# sapflux_base_v2.net
KiCad netlist of a schematic drawn in EAGLE
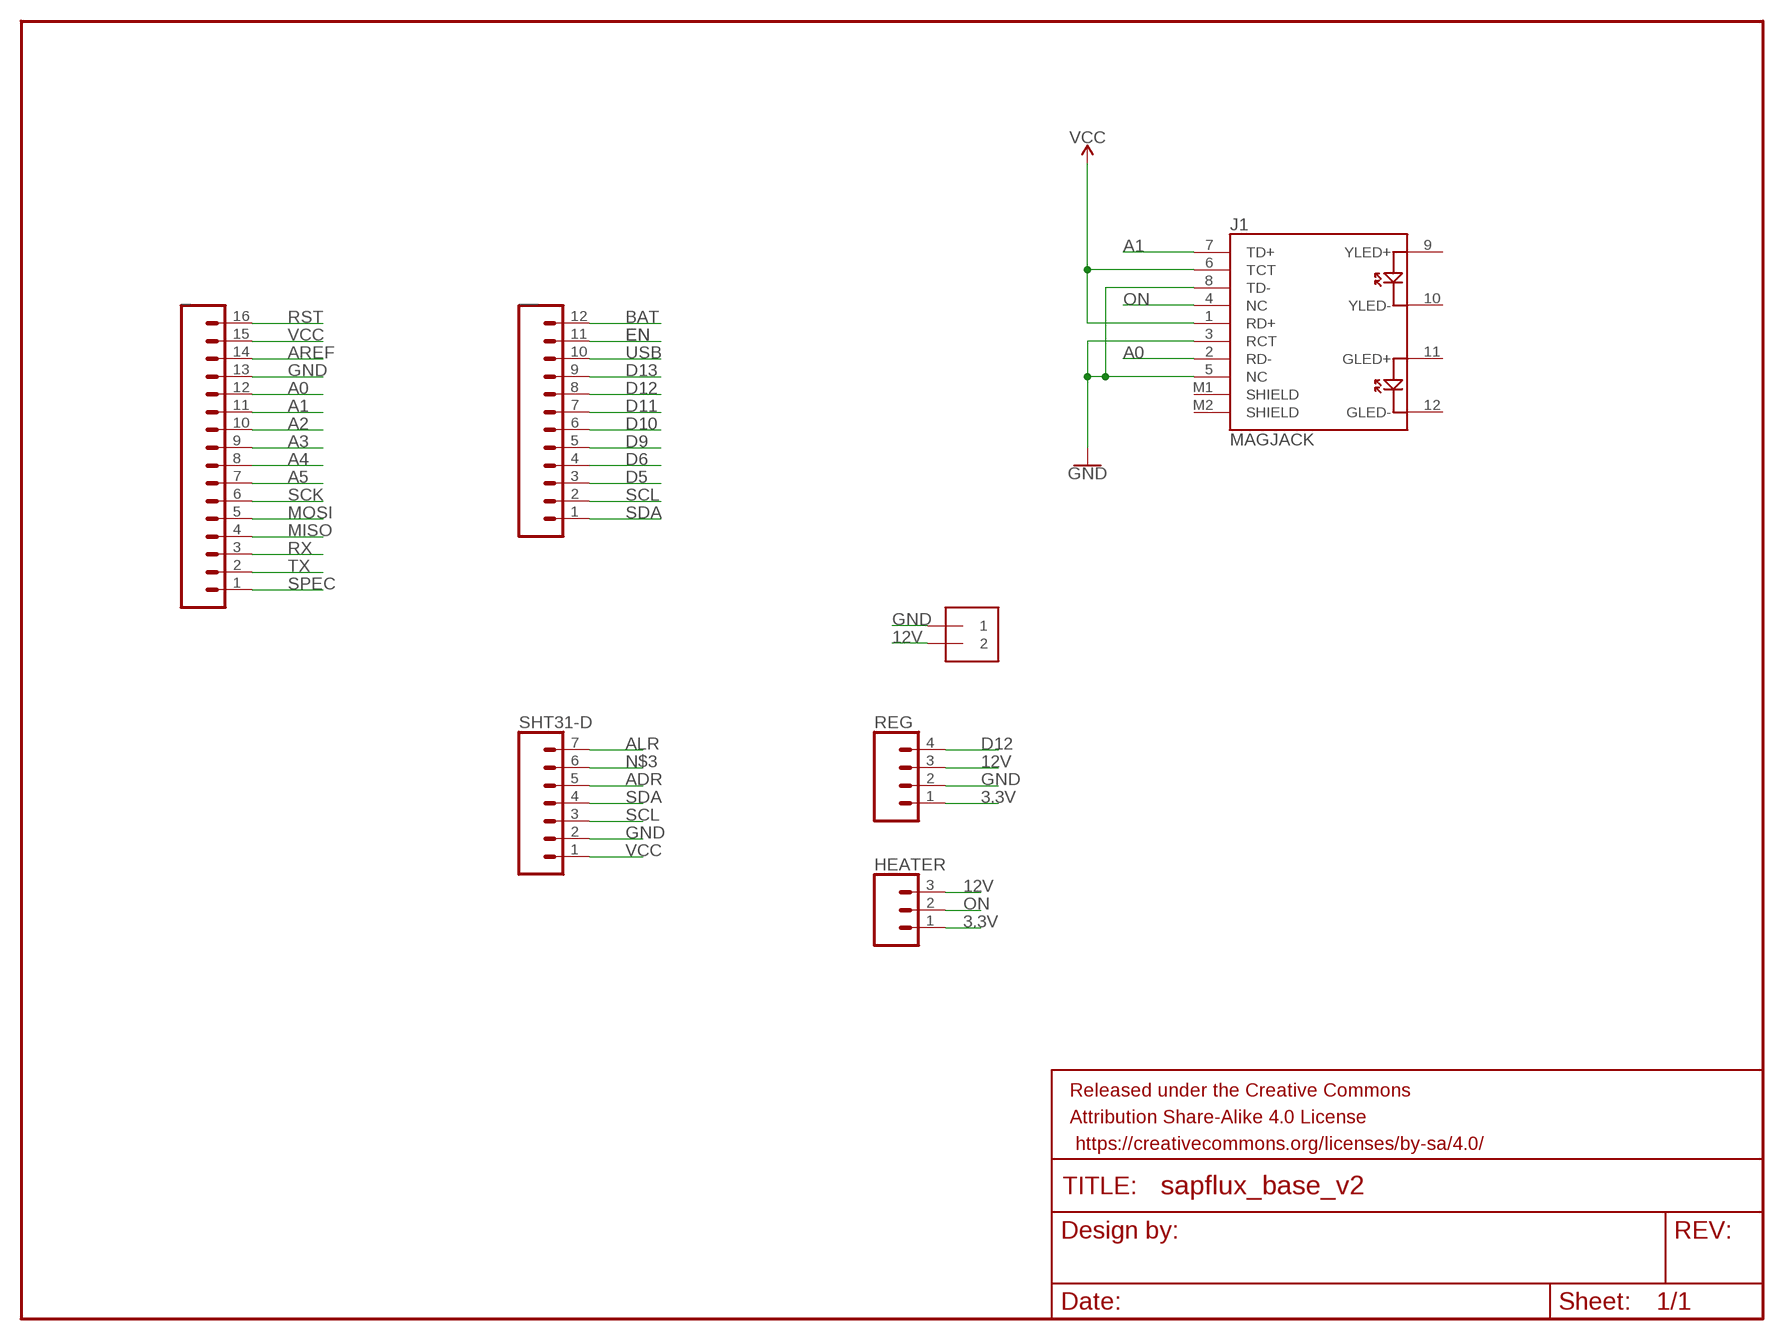
[diagram p0: schematic, sheet 1]

(export (version "E")
  (design (tool "Eeschema 10.0.6"))
  (components
    (comp (ref ".")
      (value "1X2-3.5MM")
      (footprint "eagle-import:1X2-3.5MM")
      (libsource (lib "eagle-import") (part "1X2-3.5MM"))
    )
    (comp (ref "FRAME1")
      (value "FRAME-LETTER")
      (footprint "eagle-import:CREATIVE_COMMONS")
      (libsource (lib "eagle-import") (part "FRAME-LETTER"))
    )
    (comp (ref "HEATER")
      (value "CONN_03")
      (footprint "eagle-import:1X03")
      (libsource (lib "eagle-import") (part "CONN_03"))
    )
    (comp (ref "J1")
      (value "MAGJACK")
      (footprint "eagle-import:MAGJACK")
      (libsource (lib "eagle-import") (part "MAGJACK"))
    )
    (comp (ref "REG")
      (value "CONN_04")
      (footprint "eagle-import:1X04")
      (libsource (lib "eagle-import") (part "CONN_04"))
    )
    (comp (ref "SHT31-D")
      (value "CONN_07")
      (footprint "eagle-import:1X07")
      (libsource (lib "eagle-import") (part "CONN_07"))
    )
    (comp (ref "_")
      (value "CONN_16")
      (footprint "eagle-import:1X16")
      (libsource (lib "eagle-import") (part "CONN_16"))
    )
    (comp (ref "__")
      (value "CONN_12")
      (footprint "eagle-import:1X12")
      (libsource (lib "eagle-import") (part "CONN_12"))
    )
  )
  (nets
    (net (code "1") (name "/3.3V") (class "Default")
      (node (ref "HEATER") (pin "1") (pinfunction "1_1") (pintype "passive"))
      (node (ref "REG") (pin "1") (pinfunction "1_1") (pintype "passive"))
    )
    (net (code "2") (name "/12V") (class "Default")
      (node (ref ".") (pin "2") (pinfunction "2_2") (pintype "passive"))
      (node (ref "HEATER") (pin "3") (pinfunction "3_3") (pintype "passive"))
      (node (ref "REG") (pin "3") (pinfunction "3_3") (pintype "passive"))
    )
    (net (code "3") (name "/A0") (class "Default")
      (node (ref "J1") (pin "2") (pinfunction "RD-_2") (pintype "bidirectional"))
      (node (ref "_") (pin "12") (pinfunction "12_12") (pintype "passive"))
    )
    (net (code "4") (name "/A1") (class "Default")
      (node (ref "J1") (pin "7") (pinfunction "TD+_7") (pintype "bidirectional"))
      (node (ref "_") (pin "11") (pinfunction "11_11") (pintype "passive"))
    )
    (net (code "5") (name "/A2") (class "Default")
      (node (ref "_") (pin "10") (pinfunction "10_10") (pintype "passive"))
    )
    (net (code "6") (name "/A3") (class "Default")
      (node (ref "_") (pin "9") (pinfunction "9_9") (pintype "passive"))
    )
    (net (code "7") (name "/A4") (class "Default")
      (node (ref "_") (pin "8") (pinfunction "8_8") (pintype "passive"))
    )
    (net (code "8") (name "/A5") (class "Default")
      (node (ref "_") (pin "7") (pinfunction "7_7") (pintype "passive"))
    )
    (net (code "9") (name "/ADR") (class "Default")
      (node (ref "SHT31-D") (pin "5") (pinfunction "5_5") (pintype "passive"))
    )
    (net (code "10") (name "/ALR") (class "Default")
      (node (ref "SHT31-D") (pin "7") (pinfunction "7_7") (pintype "passive"))
    )
    (net (code "11") (name "/AREF") (class "Default")
      (node (ref "_") (pin "14") (pinfunction "14_14") (pintype "passive"))
    )
    (net (code "12") (name "/BAT") (class "Default")
      (node (ref "__") (pin "12") (pinfunction "12_12") (pintype "passive"))
    )
    (net (code "13") (name "/D5") (class "Default")
      (node (ref "__") (pin "3") (pinfunction "3_3") (pintype "passive"))
    )
    (net (code "14") (name "/D6") (class "Default")
      (node (ref "__") (pin "4") (pinfunction "4_4") (pintype "passive"))
    )
    (net (code "15") (name "/D9") (class "Default")
      (node (ref "__") (pin "5") (pinfunction "5_5") (pintype "passive"))
    )
    (net (code "16") (name "/D10") (class "Default")
      (node (ref "__") (pin "6") (pinfunction "6_6") (pintype "passive"))
    )
    (net (code "17") (name "/D11") (class "Default")
      (node (ref "__") (pin "7") (pinfunction "7_7") (pintype "passive"))
    )
    (net (code "18") (name "/D12") (class "Default")
      (node (ref "REG") (pin "4") (pinfunction "4_4") (pintype "passive"))
      (node (ref "__") (pin "8") (pinfunction "8_8") (pintype "passive"))
    )
    (net (code "19") (name "/D13") (class "Default")
      (node (ref "__") (pin "9") (pinfunction "9_9") (pintype "passive"))
    )
    (net (code "20") (name "/EN") (class "Default")
      (node (ref "__") (pin "11") (pinfunction "11_11") (pintype "passive"))
    )
    (net (code "21") (name "/MISO") (class "Default")
      (node (ref "_") (pin "4") (pinfunction "4_4") (pintype "passive"))
    )
    (net (code "22") (name "/MOSI") (class "Default")
      (node (ref "_") (pin "5") (pinfunction "5_5") (pintype "passive"))
    )
    (net (code "23") (name "/N$3") (class "Default")
      (node (ref "SHT31-D") (pin "6") (pinfunction "6_6") (pintype "passive"))
    )
    (net (code "24") (name "/ON") (class "Default")
      (node (ref "HEATER") (pin "2") (pinfunction "2_2") (pintype "passive"))
      (node (ref "J1") (pin "4") (pinfunction "NC_4") (pintype "bidirectional"))
    )
    (net (code "25") (name "/RST") (class "Default")
      (node (ref "_") (pin "16") (pinfunction "16_16") (pintype "passive"))
    )
    (net (code "26") (name "/RX") (class "Default")
      (node (ref "_") (pin "3") (pinfunction "3_3") (pintype "passive"))
    )
    (net (code "27") (name "/SCK") (class "Default")
      (node (ref "_") (pin "6") (pinfunction "6_6") (pintype "passive"))
    )
    (net (code "28") (name "/SCL") (class "Default")
      (node (ref "SHT31-D") (pin "3") (pinfunction "3_3") (pintype "passive"))
      (node (ref "__") (pin "2") (pinfunction "2_2") (pintype "passive"))
    )
    (net (code "29") (name "/SDA") (class "Default")
      (node (ref "SHT31-D") (pin "4") (pinfunction "4_4") (pintype "passive"))
      (node (ref "__") (pin "1") (pinfunction "1_1") (pintype "passive"))
    )
    (net (code "30") (name "/SPEC") (class "Default")
      (node (ref "_") (pin "1") (pinfunction "1_1") (pintype "passive"))
    )
    (net (code "31") (name "/TX") (class "Default")
      (node (ref "_") (pin "2") (pinfunction "2_2") (pintype "passive"))
    )
    (net (code "32") (name "/USB") (class "Default")
      (node (ref "__") (pin "10") (pinfunction "10_10") (pintype "passive"))
    )
    (net (code "33") (name "GND") (class "Default")
      (node (ref ".") (pin "1") (pinfunction "1_1") (pintype "passive"))
      (node (ref "J1") (pin "3") (pinfunction "RCT_3") (pintype "bidirectional"))
      (node (ref "J1") (pin "5") (pinfunction "NC_5") (pintype "bidirectional"))
      (node (ref "J1") (pin "8") (pinfunction "TD-_8") (pintype "bidirectional"))
      (node (ref "REG") (pin "2") (pinfunction "2_2") (pintype "passive"))
      (node (ref "SHT31-D") (pin "2") (pinfunction "2_2") (pintype "passive"))
      (node (ref "_") (pin "13") (pinfunction "13_13") (pintype "passive"))
    )
    (net (code "34") (name "VCC") (class "Default")
      (node (ref "J1") (pin "1") (pinfunction "RD+_1") (pintype "bidirectional"))
      (node (ref "J1") (pin "6") (pinfunction "TCT_6") (pintype "bidirectional"))
      (node (ref "SHT31-D") (pin "1") (pinfunction "1_1") (pintype "passive"))
      (node (ref "_") (pin "15") (pinfunction "15_15") (pintype "passive"))
    )
    (net (code "35") (name "unconnected-(J1-GLED+-Pad11)") (class "Default")
      (node (ref "J1") (pin "11") (pinfunction "GLED+_11") (pintype "bidirectional"))
    )
    (net (code "36") (name "unconnected-(J1-GLED--Pad12)") (class "Default")
      (node (ref "J1") (pin "12") (pinfunction "GLED-_12") (pintype "bidirectional"))
    )
    (net (code "37") (name "unconnected-(J1-SHIELD-PadM1)") (class "Default")
      (node (ref "J1") (pin "M1") (pinfunction "SHIELD_M1") (pintype "bidirectional"))
    )
    (net (code "38") (name "unconnected-(J1-SHIELD-PadM2)") (class "Default")
      (node (ref "J1") (pin "M2") (pinfunction "SHIELD_M2") (pintype "bidirectional"))
    )
    (net (code "39") (name "unconnected-(J1-YLED+-Pad9)") (class "Default")
      (node (ref "J1") (pin "9") (pinfunction "YLED+_9") (pintype "bidirectional"))
    )
    (net (code "40") (name "unconnected-(J1-YLED--Pad10)") (class "Default")
      (node (ref "J1") (pin "10") (pinfunction "YLED-_10") (pintype "bidirectional"))
    )
  )
)
